# RX-FM-Radio-Simple-BF494.net
KiCad netlist of a schematic drawn in EAGLE
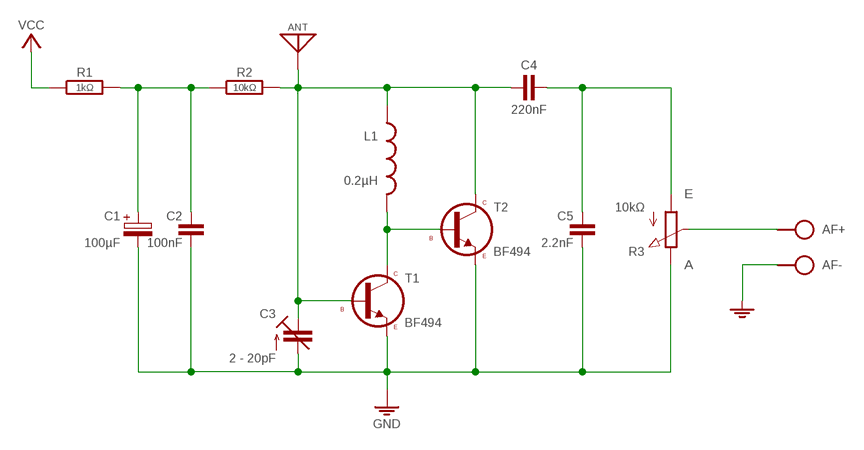
[diagram p0: schematic, sheet 1]

(export (version "E")
  (design (tool "Eeschema 10.0.6"))
  (components
    (comp (ref "AF")
      (value "SPAD+-+-")
      (footprint "eagle-import:SPAD+-")
      (libsource (lib "eagle-import") (part "SPAD+-+-"))
    )
    (comp (ref "ANT")
      (value "ANT")
      (footprint "eagle-import:SPAD")
      (libsource (lib "eagle-import") (part "ANT"))
    )
    (comp (ref "BAT")
      (value "VCC_GNDL")
      (footprint "eagle-import:SPAD-+")
      (libsource (lib "eagle-import") (part "VCC_GNDL"))
    )
    (comp (ref "C1")
      (value "100µF")
      (footprint "eagle-import:E2,5-5_V")
      (libsource (lib "eagle-import") (part "CPOLE2,5-5/V"))
    )
    (comp (ref "C2")
      (value "100nF")
      (footprint "eagle-import:C050-020X036_V")
      (libsource (lib "eagle-import") (part "C050-020X036/V"))
    )
    (comp (ref "C3")
      (value "2 - 20pF")
      (footprint "eagle-import:TRIM-2222-808")
      (libsource (lib "eagle-import") (part "C-TR-PH201272222-808-2PIND"))
    )
    (comp (ref "C4")
      (value "220nF")
      (footprint "eagle-import:C050-020X044")
      (libsource (lib "eagle-import") (part "C-H050-020X044"))
    )
    (comp (ref "C5")
      (value "2.2nF")
      (footprint "eagle-import:C050-020X036_V")
      (libsource (lib "eagle-import") (part "C050-020X036/V"))
    )
    (comp (ref "L1")
      (value "0.2µH")
      (footprint "eagle-import:L-10_10X")
      (libsource (lib "eagle-import") (part "L10/10X"))
    )
    (comp (ref "R1")
      (value "1kΩ")
      (footprint "eagle-import:0204_10")
      (libsource (lib "eagle-import") (part "R-H0204/10"))
    )
    (comp (ref "R2")
      (value "10kΩ")
      (footprint "eagle-import:0204_10")
      (libsource (lib "eagle-import") (part "R-H0204/10"))
    )
    (comp (ref "R3")
      (value "10kΩ")
      (footprint "eagle-import:POT")
      (libsource (lib "eagle-import") (part "POT"))
    )
    (comp (ref "T1")
      (value "BF494")
      (footprint "eagle-import:TO92-CEB")
      (libsource (lib "eagle-import") (part "BF494"))
    )
    (comp (ref "T2")
      (value "BF494")
      (footprint "eagle-import:TO92-CEB")
      (libsource (lib "eagle-import") (part "BF494"))
    )
  )
  (nets
    (net (code "1") (name "GND") (class "Default")
      (node (ref "AF") (pin "1") (pinfunction "P$1_1") (pintype "passive"))
      (node (ref "BAT") (pin "1") (pinfunction "GND_1") (pintype "power_in"))
      (node (ref "C1") (pin "-") (pinfunction "-_-") (pintype "passive"))
      (node (ref "C2") (pin "2") (pinfunction "2_2") (pintype "passive"))
      (node (ref "C3") (pin "2") (pinfunction "A_2") (pintype "passive"))
      (node (ref "C5") (pin "2") (pinfunction "2_2") (pintype "passive"))
      (node (ref "R3") (pin "E") (pinfunction "E_E") (pintype "passive"))
      (node (ref "T1") (pin "E") (pinfunction "E_E") (pintype "passive"))
      (node (ref "T2") (pin "E") (pinfunction "E_E") (pintype "passive"))
    )
    (net (code "2") (name "Net-(AFA-P$1)") (class "Default")
      (node (ref "AF") (pin "2") (pinfunction "P$1_2") (pintype "passive"))
      (node (ref "R3") (pin "S") (pinfunction "S_S") (pintype "passive"))
    )
    (net (code "3") (name "Net-(BATA-VCC)") (class "Default")
      (node (ref "BAT") (pin "2") (pinfunction "VCC_2") (pintype "power_in"))
      (node (ref "R1") (pin "1") (pinfunction "1_1") (pintype "passive"))
    )
    (net (code "4") (name "Net-(C1-Pad+)") (class "Default")
      (node (ref "C1") (pin "+") (pinfunction "+_+") (pintype "passive"))
      (node (ref "C2") (pin "1") (pinfunction "1_1") (pintype "passive"))
      (node (ref "R1") (pin "2") (pinfunction "2_2") (pintype "passive"))
      (node (ref "R2") (pin "1") (pinfunction "1_1") (pintype "passive"))
    )
    (net (code "5") (name "Net-(C3-E)") (class "Default")
      (node (ref "ANT") (pin "1") (pinfunction "1_1") (pintype "output"))
      (node (ref "C3") (pin "3") (pinfunction "E_3") (pintype "passive"))
      (node (ref "C4") (pin "1") (pinfunction "1_1") (pintype "passive"))
      (node (ref "L1") (pin "P$1") (pinfunction "1_P$1") (pintype "passive"))
      (node (ref "R2") (pin "2") (pinfunction "2_2") (pintype "passive"))
      (node (ref "T1") (pin "B") (pinfunction "B_B") (pintype "passive"))
      (node (ref "T2") (pin "C") (pinfunction "C_C") (pintype "passive"))
    )
    (net (code "6") (name "Net-(C4-Pad2)") (class "Default")
      (node (ref "C4") (pin "2") (pinfunction "2_2") (pintype "passive"))
      (node (ref "C5") (pin "1") (pinfunction "1_1") (pintype "passive"))
      (node (ref "R3") (pin "A") (pinfunction "A_A") (pintype "passive"))
    )
    (net (code "7") (name "Net-(L1-2)") (class "Default")
      (node (ref "L1") (pin "P$2") (pinfunction "2_P$2") (pintype "passive"))
      (node (ref "T1") (pin "C") (pinfunction "C_C") (pintype "passive"))
      (node (ref "T2") (pin "B") (pinfunction "B_B") (pintype "passive"))
    )
  )
)
